# Controller.net
KiCad netlist of a schematic drawn in Altium Designer
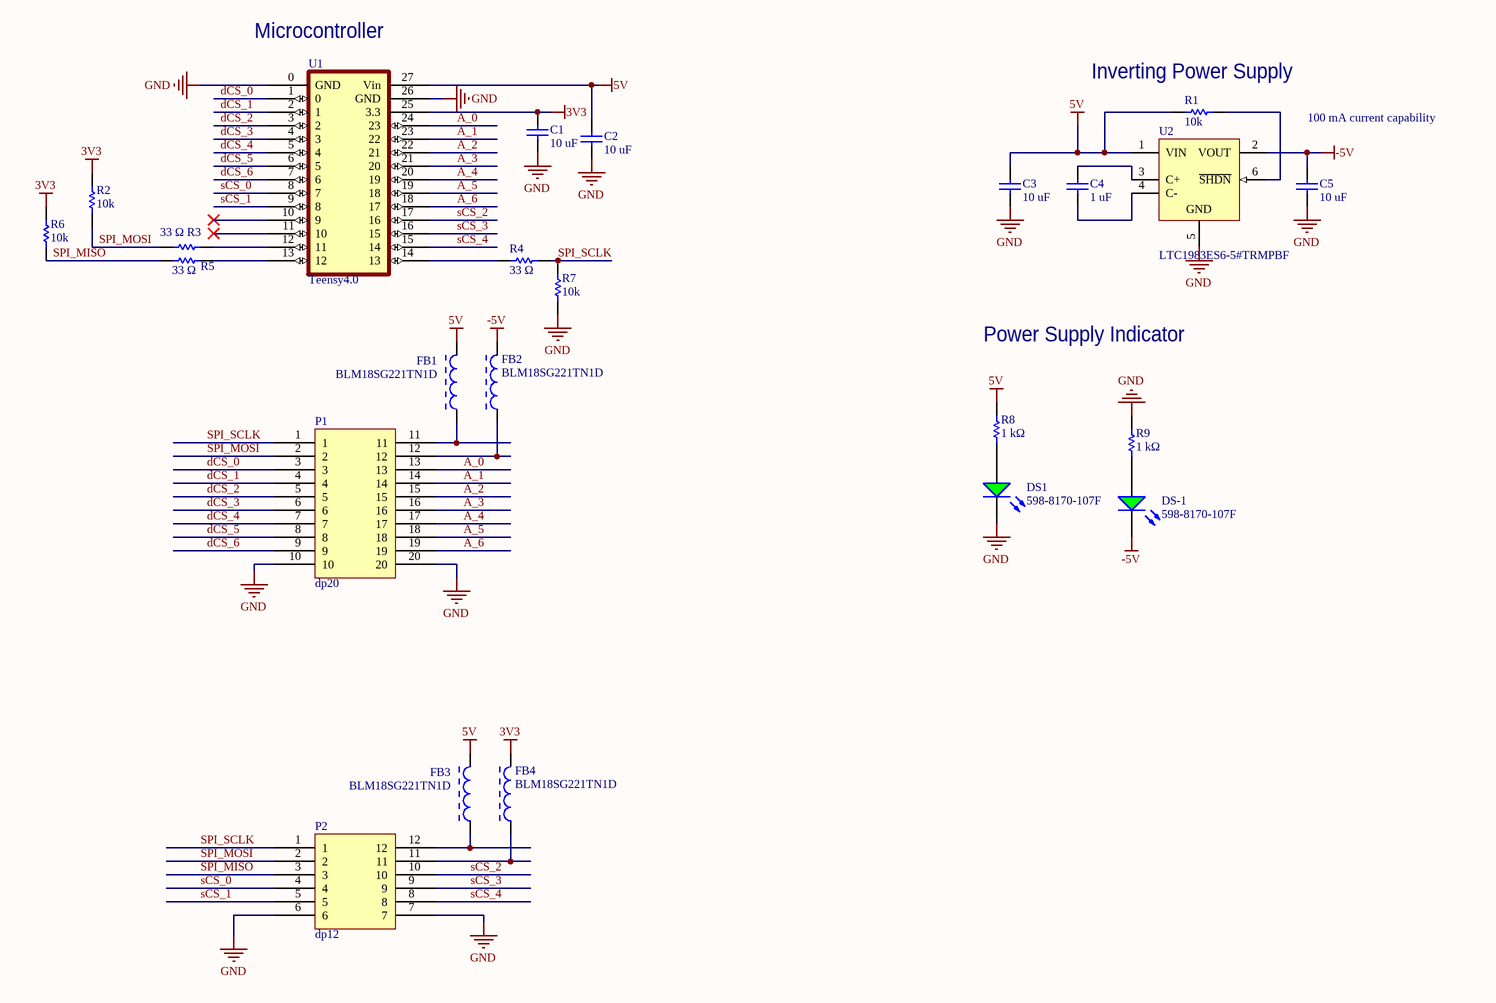
[diagram p0: Controller_root.SchDoc]

(export (version "E")
  (design (tool "Eeschema 10.0.6"))
  (components
    (comp (ref "C1")
      (value "10 uF")
      (footprint "CAPC1608X90X20ML10")
      (description "Chip Capacitor, 10 uF, +/- 10%, 10 V, -55 to 85 degC, 0603 (1608 Metric), RoHS, Tape and Reel")
      (fields
        (field (name "PCN PART NUMBER") "MLCCPartNumberChange30/Nov/2012")
        (field (name "TOLERANCE") "±10%")
      )
      (libsource (lib "Altium Content Vault") (part "CAP-NP-2"))
    )
    (comp (ref "C2")
      (value "10 uF")
      (footprint "CAPC1608X90X20ML10")
      (description "Chip Capacitor, 10 uF, +/- 10%, 10 V, -55 to 85 degC, 0603 (1608 Metric), RoHS, Tape and Reel")
      (fields
        (field (name "PCN PART NUMBER") "MLCCPartNumberChange30/Nov/2012")
        (field (name "TOLERANCE") "±10%")
      )
      (libsource (lib "Altium Content Vault") (part "CAP-NP-2"))
    )
    (comp (ref "C3")
      (value "10 uF")
      (footprint "CAPC1608X90X20ML10")
      (description "Chip Capacitor, 10 uF, +/- 10%, 10 V, -55 to 85 degC, 0603 (1608 Metric), RoHS, Tape and Reel")
      (fields
        (field (name "PCN PART NUMBER") "MLCCPartNumberChange30/Nov/2012")
        (field (name "TOLERANCE") "±10%")
      )
      (libsource (lib "Altium Content Vault") (part "CAP-NP-2"))
    )
    (comp (ref "C4")
      (value "1 uF")
      (footprint "CAPC1608X90X20ML10")
      (description "Chip Capacitor, 1 uF, +/- 10%, 50 V, -55 to 85 degC, 0603 (1608 Metric), RoHS, Tape and Reel")
      (fields
        (field (name "MANUFACTURER") "TDK")
        (field (name "PCN PART NUMBER") "MLCCPartNumberChange30/Nov/2012")
      )
      (libsource (lib "Altium Content Vault") (part "CAP-NP-2"))
    )
    (comp (ref "C5")
      (value "10 uF")
      (footprint "CAPC1608X90X20ML10")
      (description "Chip Capacitor, 10 uF, +/- 10%, 10 V, -55 to 85 degC, 0603 (1608 Metric), RoHS, Tape and Reel")
      (fields
        (field (name "PCN PART NUMBER") "MLCCPartNumberChange30/Nov/2012")
        (field (name "TOLERANCE") "±10%")
      )
      (libsource (lib "Altium Content Vault") (part "CAP-NP-2"))
    )
    (comp (ref "DS-1")
      (value "598-8170-107F")
      (footprint "DIAL-0805-2_V")
      (description "Single Color, 2 V, -30 to 85 degC, 2-Pin SMD (0805), RoHS, Tape and Reel")
      (fields (field (name "MANUFACTURER") "Dialight"))
      (libsource (lib "Altium Content Vault") (part "LED-GREEN-AK-2"))
    )
    (comp (ref "DS1")
      (value "598-8170-107F")
      (footprint "DIAL-0805-2_V")
      (description "Single Color, 2 V, -30 to 85 degC, 2-Pin SMD (0805), RoHS, Tape and Reel")
      (fields (field (name "MANUFACTURER") "Dialight"))
      (libsource (lib "Altium Content Vault") (part "LED-GREEN-AK-2"))
    )
    (comp (ref "FB1")
      (value "BLM18SG221TN1D")
      (footprint "MURA-BLM18SG-B25-CHIP-2_V1")
      (fields (field (name "MANUFACTURER") "Murata"))
      (libsource (lib "Altium Content Vault") (part "MURA-FB-2"))
    )
    (comp (ref "FB2")
      (value "BLM18SG221TN1D")
      (footprint "MURA-BLM18SG-B25-CHIP-2_V1")
      (fields (field (name "MANUFACTURER") "Murata"))
      (libsource (lib "Altium Content Vault") (part "MURA-FB-2"))
    )
    (comp (ref "FB3")
      (value "BLM18SG221TN1D")
      (footprint "MURA-BLM18SG-B25-CHIP-2_V1")
      (fields (field (name "MANUFACTURER") "Murata"))
      (libsource (lib "Altium Content Vault") (part "MURA-FB-2"))
    )
    (comp (ref "FB4")
      (value "BLM18SG221TN1D")
      (footprint "MURA-BLM18SG-B25-CHIP-2_V1")
      (fields (field (name "MANUFACTURER") "Murata"))
      (libsource (lib "Altium Content Vault") (part "MURA-FB-2"))
    )
    (comp (ref "P1") (value "dp20") (footprint "dp20-900") (libsource (lib "myComponents") (part "dp20")))
    (comp (ref "P2") (value "dp12") (footprint "dp12-900") (libsource (lib "myComponents") (part "dp12")))
    (comp (ref "R1")
      (value "10k")
      (footprint "RESC1609X55X30ML15T15")
      (description "Chip Resistor, 10 KOhm, +/- 1%, 0.1 W, -55 to 155 degC, 0603 (1608 Metric), RoHS, Tape and Reel")
      (fields (field (name "TOLERANCE") "1%") (field (name "MANUFACTURER") "Panasonic"))
      (libsource (lib "Altium Content Vault") (part "RES-2"))
    )
    (comp (ref "R2")
      (value "10k")
      (footprint "RESC1609X55X30ML15T15")
      (description "Chip Resistor, 10 KOhm, +/- 1%, 0.1 W, -55 to 155 degC, 0603 (1608 Metric), RoHS, Tape and Reel")
      (fields (field (name "TOLERANCE") "1%") (field (name "MANUFACTURER") "Panasonic"))
      (libsource (lib "Altium Content Vault") (part "RES-2"))
    )
    (comp (ref "R3")
      (value "33 Ω")
      (footprint "RESC1609X50X30NL10T20")
      (fields (field (name "PART NUMBER") "CRCW060333R0FKEA") (field (name "MANUFACTURER") "Vishay Dale"))
      (libsource (lib "Altium Content Vault") (part "RES"))
    )
    (comp (ref "R4")
      (value "33 Ω")
      (footprint "RESC1609X50X30NL10T20")
      (fields (field (name "PART NUMBER") "CRCW060333R0FKEA") (field (name "MANUFACTURER") "Vishay Dale"))
      (libsource (lib "Altium Content Vault") (part "RES"))
    )
    (comp (ref "R5")
      (value "33 Ω")
      (footprint "RESC1609X50X30NL10T20")
      (fields (field (name "PART NUMBER") "CRCW060333R0FKEA") (field (name "MANUFACTURER") "Vishay Dale"))
      (libsource (lib "Altium Content Vault") (part "RES"))
    )
    (comp (ref "R6")
      (value "10k")
      (footprint "RESC1609X55X30ML15T15")
      (description "Chip Resistor, 10 KOhm, +/- 1%, 0.1 W, -55 to 155 degC, 0603 (1608 Metric), RoHS, Tape and Reel")
      (fields (field (name "TOLERANCE") "1%") (field (name "MANUFACTURER") "Panasonic"))
      (libsource (lib "Altium Content Vault") (part "RES-2"))
    )
    (comp (ref "R7")
      (value "10k")
      (footprint "RESC1609X55X30ML15T15")
      (description "Chip Resistor, 10 KOhm, +/- 1%, 0.1 W, -55 to 155 degC, 0603 (1608 Metric), RoHS, Tape and Reel")
      (fields (field (name "TOLERANCE") "1%") (field (name "MANUFACTURER") "Panasonic"))
      (libsource (lib "Altium Content Vault") (part "RES-2"))
    )
    (comp (ref "R8")
      (value "1 kΩ")
      (footprint "RESC1608X55X30LL15T15")
      (fields (field (name "PART NUMBER") "ERJ-3EKF1001V") (field (name "MANUFACTURER") "Panasonic"))
      (libsource (lib "Altium Content Vault") (part "RES"))
    )
    (comp (ref "R9")
      (value "1 kΩ")
      (footprint "RESC1608X55X30LL15T15")
      (fields (field (name "PART NUMBER") "ERJ-3EKF1001V") (field (name "MANUFACTURER") "Panasonic"))
      (libsource (lib "Altium Content Vault") (part "RES"))
    )
    (comp (ref "U1")
      (value "Teensy4.0")
      (footprint "DIP28-600")
      (libsource (lib "myComponents") (part "Teensy4.0"))
    )
    (comp (ref "U2")
      (value "LTC1983ES6-5#TRMPBF")
      (footprint "LT-S6-6-TSOT-23_N")
      (fields (field (name "MANUFACTURER") "Linear Technology"))
      (libsource (lib "Altium Content Vault") (part "LT-LTC1983-S6-6"))
    )
  )
  (nets
    (net (code "1") (name "-5V") (class "Default")
      (node (ref "C5") (pin "2") (pinfunction "2_2") (pintype "passive"))
      (node (ref "DS-1") (pin "2") (pinfunction "K_2") (pintype "passive"))
      (node (ref "FB2") (pin "2") (pinfunction "2_2") (pintype "passive"))
      (node (ref "U2") (pin "2") (pinfunction "VOUT_2") (pintype "power_in"))
    )
    (net (code "2") (name "/A_0") (class "Default")
      (node (ref "P1") (pin "13") (pinfunction "13_13") (pintype "passive"))
      (node (ref "U1") (pin "24") (pinfunction "23_24") (pintype "bidirectional"))
    )
    (net (code "3") (name "/A_1") (class "Default")
      (node (ref "P1") (pin "14") (pinfunction "14_14") (pintype "passive"))
      (node (ref "U1") (pin "23") (pinfunction "22_23") (pintype "bidirectional"))
    )
    (net (code "4") (name "/A_2") (class "Default")
      (node (ref "P1") (pin "15") (pinfunction "15_15") (pintype "passive"))
      (node (ref "U1") (pin "22") (pinfunction "21_22") (pintype "bidirectional"))
    )
    (net (code "5") (name "/A_3") (class "Default")
      (node (ref "P1") (pin "16") (pinfunction "16_16") (pintype "passive"))
      (node (ref "U1") (pin "21") (pinfunction "20_21") (pintype "bidirectional"))
    )
    (net (code "6") (name "/A_4") (class "Default")
      (node (ref "P1") (pin "17") (pinfunction "17_17") (pintype "passive"))
      (node (ref "U1") (pin "20") (pinfunction "19_20") (pintype "bidirectional"))
    )
    (net (code "7") (name "/A_5") (class "Default")
      (node (ref "P1") (pin "18") (pinfunction "18_18") (pintype "passive"))
      (node (ref "U1") (pin "19") (pinfunction "18_19") (pintype "bidirectional"))
    )
    (net (code "8") (name "/A_6") (class "Default")
      (node (ref "P1") (pin "19") (pinfunction "19_19") (pintype "passive"))
      (node (ref "U1") (pin "18") (pinfunction "17_18") (pintype "bidirectional"))
    )
    (net (code "9") (name "/SPI_MISO") (class "Default")
      (node (ref "P2") (pin "3") (pinfunction "3_3") (pintype "passive"))
      (node (ref "R5") (pin "1") (pinfunction "1_1") (pintype "passive"))
      (node (ref "R6") (pin "2") (pinfunction "2_2") (pintype "passive"))
    )
    (net (code "10") (name "/SPI_MOSI") (class "Default")
      (node (ref "P1") (pin "2") (pinfunction "2_2") (pintype "passive"))
      (node (ref "P2") (pin "2") (pinfunction "2_2") (pintype "passive"))
      (node (ref "R2") (pin "1") (pinfunction "1_1") (pintype "passive"))
      (node (ref "R3") (pin "1") (pinfunction "1_1") (pintype "passive"))
    )
    (net (code "11") (name "/SPI_SCLK") (class "Default")
      (node (ref "P1") (pin "1") (pinfunction "1_1") (pintype "passive"))
      (node (ref "P2") (pin "1") (pinfunction "1_1") (pintype "passive"))
      (node (ref "R4") (pin "2") (pinfunction "2_2") (pintype "passive"))
      (node (ref "R7") (pin "2") (pinfunction "2_2") (pintype "passive"))
    )
    (net (code "12") (name "/dCS_0") (class "Default")
      (node (ref "P1") (pin "3") (pinfunction "3_3") (pintype "passive"))
      (node (ref "U1") (pin "1") (pinfunction "0_1") (pintype "bidirectional"))
    )
    (net (code "13") (name "/dCS_1") (class "Default")
      (node (ref "P1") (pin "4") (pinfunction "4_4") (pintype "passive"))
      (node (ref "U1") (pin "2") (pinfunction "1_2") (pintype "bidirectional"))
    )
    (net (code "14") (name "/dCS_2") (class "Default")
      (node (ref "P1") (pin "5") (pinfunction "5_5") (pintype "passive"))
      (node (ref "U1") (pin "3") (pinfunction "2_3") (pintype "bidirectional"))
    )
    (net (code "15") (name "/dCS_3") (class "Default")
      (node (ref "P1") (pin "6") (pinfunction "6_6") (pintype "passive"))
      (node (ref "U1") (pin "4") (pinfunction "3_4") (pintype "bidirectional"))
    )
    (net (code "16") (name "/dCS_4") (class "Default")
      (node (ref "P1") (pin "7") (pinfunction "7_7") (pintype "passive"))
      (node (ref "U1") (pin "5") (pinfunction "4_5") (pintype "bidirectional"))
    )
    (net (code "17") (name "/dCS_5") (class "Default")
      (node (ref "P1") (pin "8") (pinfunction "8_8") (pintype "passive"))
      (node (ref "U1") (pin "6") (pinfunction "5_6") (pintype "bidirectional"))
    )
    (net (code "18") (name "/dCS_6") (class "Default")
      (node (ref "P1") (pin "9") (pinfunction "9_9") (pintype "passive"))
      (node (ref "U1") (pin "7") (pinfunction "6_7") (pintype "bidirectional"))
    )
    (net (code "19") (name "/sCS_0") (class "Default")
      (node (ref "P2") (pin "4") (pinfunction "4_4") (pintype "passive"))
      (node (ref "U1") (pin "8") (pinfunction "7_8") (pintype "bidirectional"))
    )
    (net (code "20") (name "/sCS_1") (class "Default")
      (node (ref "P2") (pin "5") (pinfunction "5_5") (pintype "passive"))
      (node (ref "U1") (pin "9") (pinfunction "8_9") (pintype "bidirectional"))
    )
    (net (code "21") (name "/sCS_2") (class "Default")
      (node (ref "P2") (pin "10") (pinfunction "10_10") (pintype "passive"))
      (node (ref "U1") (pin "17") (pinfunction "16_17") (pintype "bidirectional"))
    )
    (net (code "22") (name "/sCS_3") (class "Default")
      (node (ref "P2") (pin "9") (pinfunction "9_9") (pintype "passive"))
      (node (ref "U1") (pin "16") (pinfunction "15_16") (pintype "bidirectional"))
    )
    (net (code "23") (name "/sCS_4") (class "Default")
      (node (ref "P2") (pin "8") (pinfunction "8_8") (pintype "passive"))
      (node (ref "U1") (pin "15") (pinfunction "14_15") (pintype "bidirectional"))
    )
    (net (code "24") (name "3V3") (class "Default")
      (node (ref "C1") (pin "2") (pinfunction "2_2") (pintype "passive"))
      (node (ref "FB4") (pin "2") (pinfunction "2_2") (pintype "passive"))
      (node (ref "R2") (pin "2") (pinfunction "2_2") (pintype "passive"))
      (node (ref "R6") (pin "1") (pinfunction "1_1") (pintype "passive"))
      (node (ref "U1") (pin "25") (pinfunction "3.3_25") (pintype "power_in"))
    )
    (net (code "25") (name "5V") (class "Default")
      (node (ref "C2") (pin "2") (pinfunction "2_2") (pintype "passive"))
      (node (ref "C3") (pin "2") (pinfunction "2_2") (pintype "passive"))
      (node (ref "FB1") (pin "2") (pinfunction "2_2") (pintype "passive"))
      (node (ref "FB3") (pin "2") (pinfunction "2_2") (pintype "passive"))
      (node (ref "R1") (pin "1") (pinfunction "1_1") (pintype "passive"))
      (node (ref "R8") (pin "2") (pinfunction "2_2") (pintype "passive"))
      (node (ref "U1") (pin "27") (pinfunction "Vin_27") (pintype "power_in"))
      (node (ref "U2") (pin "1") (pinfunction "VIN_1") (pintype "power_in"))
    )
    (net (code "26") (name "GND") (class "Default")
      (node (ref "C1") (pin "1") (pinfunction "1_1") (pintype "passive"))
      (node (ref "C2") (pin "1") (pinfunction "1_1") (pintype "passive"))
      (node (ref "C3") (pin "1") (pinfunction "1_1") (pintype "passive"))
      (node (ref "C5") (pin "1") (pinfunction "1_1") (pintype "passive"))
      (node (ref "DS1") (pin "2") (pinfunction "K_2") (pintype "passive"))
      (node (ref "P1") (pin "10") (pinfunction "10_10") (pintype "passive"))
      (node (ref "P1") (pin "20") (pinfunction "20_20") (pintype "passive"))
      (node (ref "P2") (pin "6") (pinfunction "6_6") (pintype "passive"))
      (node (ref "P2") (pin "7") (pinfunction "7_7") (pintype "passive"))
      (node (ref "R7") (pin "1") (pinfunction "1_1") (pintype "passive"))
      (node (ref "R9") (pin "2") (pinfunction "2_2") (pintype "passive"))
      (node (ref "U1") (pin "0") (pinfunction "GND_0") (pintype "power_in"))
      (node (ref "U1") (pin "26") (pinfunction "GND_26") (pintype "power_in"))
      (node (ref "U2") (pin "5") (pinfunction "GND_5") (pintype "power_in"))
    )
    (net (code "27") (name "Net-(DS-1-A)") (class "Default")
      (node (ref "DS-1") (pin "1") (pinfunction "A_1") (pintype "passive"))
      (node (ref "R9") (pin "1") (pinfunction "1_1") (pintype "passive"))
    )
    (net (code "28") (name "Net-(DS1-A)") (class "Default")
      (node (ref "DS1") (pin "1") (pinfunction "A_1") (pintype "passive"))
      (node (ref "R8") (pin "1") (pinfunction "1_1") (pintype "passive"))
    )
    (net (code "29") (name "Net-(FB1-Pad1)") (class "Default")
      (node (ref "FB1") (pin "1") (pinfunction "1_1") (pintype "passive"))
      (node (ref "P1") (pin "11") (pinfunction "11_11") (pintype "passive"))
    )
    (net (code "30") (name "Net-(FB2-Pad1)") (class "Default")
      (node (ref "FB2") (pin "1") (pinfunction "1_1") (pintype "passive"))
      (node (ref "P1") (pin "12") (pinfunction "12_12") (pintype "passive"))
    )
    (net (code "31") (name "Net-(FB3-Pad1)") (class "Default")
      (node (ref "FB3") (pin "1") (pinfunction "1_1") (pintype "passive"))
      (node (ref "P2") (pin "12") (pinfunction "12_12") (pintype "passive"))
    )
    (net (code "32") (name "Net-(FB4-Pad1)") (class "Default")
      (node (ref "FB4") (pin "1") (pinfunction "1_1") (pintype "passive"))
      (node (ref "P2") (pin "11") (pinfunction "11_11") (pintype "passive"))
    )
    (net (code "33") (name "Net-(U1-11)") (class "Default")
      (node (ref "R3") (pin "2") (pinfunction "2_2") (pintype "passive"))
      (node (ref "U1") (pin "12") (pinfunction "11_12") (pintype "bidirectional"))
    )
    (net (code "34") (name "Net-(U1-12)") (class "Default")
      (node (ref "R5") (pin "2") (pinfunction "2_2") (pintype "passive"))
      (node (ref "U1") (pin "13") (pinfunction "12_13") (pintype "bidirectional"))
    )
    (net (code "35") (name "Net-(U1-13)") (class "Default")
      (node (ref "R4") (pin "1") (pinfunction "1_1") (pintype "passive"))
      (node (ref "U1") (pin "14") (pinfunction "13_14") (pintype "bidirectional"))
    )
    (net (code "36") (name "Net-(U2-C+)") (class "Default")
      (node (ref "C4") (pin "2") (pinfunction "2_2") (pintype "passive"))
      (node (ref "U2") (pin "3") (pinfunction "C+_3") (pintype "passive"))
    )
    (net (code "37") (name "Net-(U2-C-)") (class "Default")
      (node (ref "C4") (pin "1") (pinfunction "1_1") (pintype "passive"))
      (node (ref "U2") (pin "4") (pinfunction "C-_4") (pintype "passive"))
    )
    (net (code "38") (name "Net-(U2-~{SHDN})") (class "Default")
      (node (ref "R1") (pin "2") (pinfunction "2_2") (pintype "passive"))
      (node (ref "U2") (pin "6") (pinfunction "~{SHDN}_6") (pintype "input"))
    )
    (net (code "39") (name "unconnected-(U1-9-Pad10)") (class "Default")
      (node (ref "U1") (pin "10") (pinfunction "9_10") (pintype "bidirectional+no_connect"))
    )
    (net (code "40") (name "unconnected-(U1-10-Pad11)") (class "Default")
      (node (ref "U1") (pin "11") (pinfunction "10_11") (pintype "bidirectional+no_connect"))
    )
  )
)
